# nano_v1_0.net
KiCad netlist of a schematic drawn in EAGLE
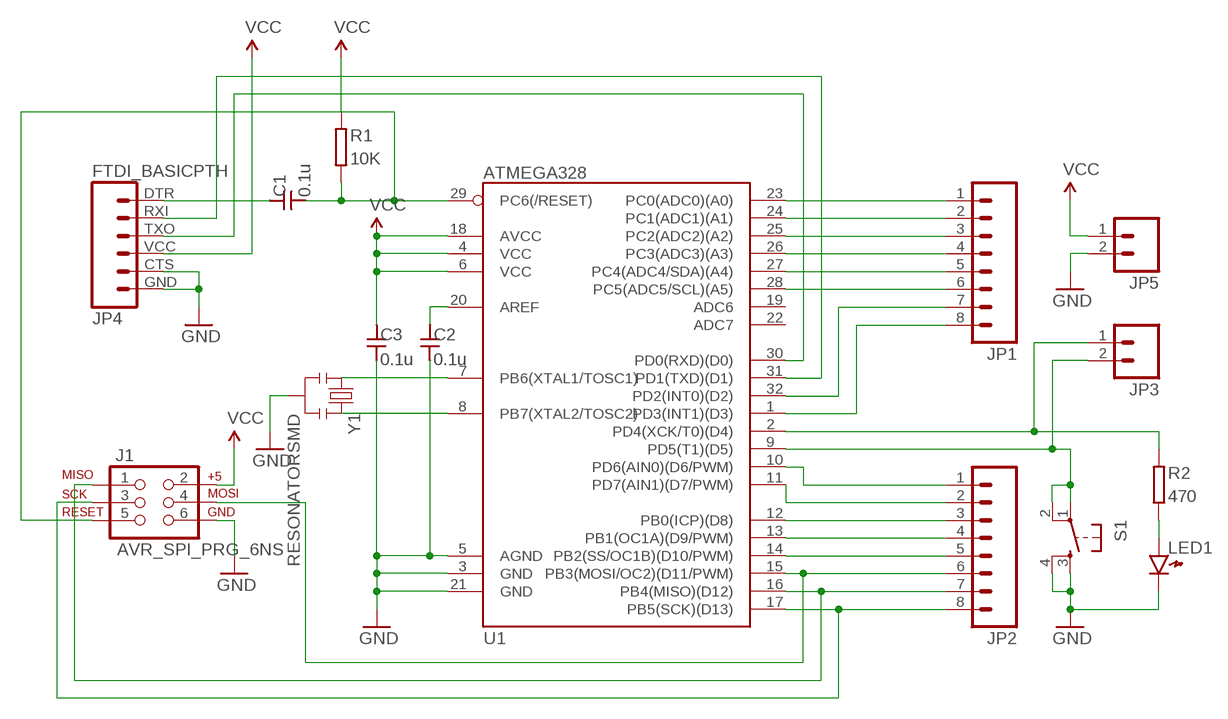
[diagram p0: schematic, sheet 1]

(export (version "E")
  (design (tool "Eeschema 10.0.6"))
  (components
    (comp (ref "C1")
      (value "0.1u")
      (footprint "eagle-import:SMD2012")
      (libsource (lib "eagle-import") (part "CAPACITOR2012"))
    )
    (comp (ref "C2")
      (value "0.1u")
      (footprint "eagle-import:SMD2012")
      (libsource (lib "eagle-import") (part "CAPACITOR2012"))
    )
    (comp (ref "C3")
      (value "0.1u")
      (footprint "eagle-import:SMD2012")
      (libsource (lib "eagle-import") (part "CAPACITOR2012"))
    )
    (comp (ref "J1")
      (value "AVR_SPI_PRG_6NS")
      (footprint "eagle-import:2X3-NS")
      (libsource (lib "eagle-import") (part "AVR_SPI_PRG_6NS"))
    )
    (comp (ref "JP1")
      (value "M081X08")
      (footprint "eagle-import:1X08")
      (libsource (lib "eagle-import") (part "M081X08"))
    )
    (comp (ref "JP2")
      (value "M081X08")
      (footprint "eagle-import:1X08")
      (libsource (lib "eagle-import") (part "M081X08"))
    )
    (comp (ref "JP3")
      (value "M02PTH")
      (footprint "eagle-import:1X02")
      (libsource (lib "eagle-import") (part "M02PTH"))
    )
    (comp (ref "JP4")
      (value "FTDI_BASICPTH")
      (footprint "eagle-import:FTDI_BASIC")
      (libsource (lib "eagle-import") (part "FTDI_BASICPTH"))
    )
    (comp (ref "JP5")
      (value "M021X02_NO_SILK")
      (footprint "eagle-import:1X02_NO_SILK")
      (libsource (lib "eagle-import") (part "M021X02_NO_SILK"))
    )
    (comp (ref "LED1")
      (value "LED2012")
      (footprint "eagle-import:LED2012")
      (libsource (lib "eagle-import") (part "LED2012"))
    )
    (comp (ref "R1")
      (value "10K")
      (footprint "eagle-import:SMD2012")
      (libsource (lib "eagle-import") (part "REGISTOR2012"))
    )
    (comp (ref "R2")
      (value "470")
      (footprint "eagle-import:SMD2012")
      (libsource (lib "eagle-import") (part "REGISTOR2012"))
    )
    (comp (ref "S1")
      (value "TAC_SWITCHSMD")
      (footprint "eagle-import:TACTILE_SWITCH_SMD")
      (libsource (lib "eagle-import") (part "TAC_SWITCHSMD"))
    )
    (comp (ref "U1")
      (value "ATMEGA328")
      (footprint "eagle-import:TQFP32-08")
      (libsource (lib "eagle-import") (part "ATMEGA328"))
    )
    (comp (ref "Y1")
      (value "RESONATORSMD")
      (footprint "eagle-import:RESONATOR-SMD")
      (libsource (lib "eagle-import") (part "RESONATORSMD"))
    )
  )
  (nets
    (net (code "1") (name "GND") (class "Default")
      (node (ref "C2") (pin "2") (pinfunction "2_2") (pintype "passive"))
      (node (ref "C3") (pin "2") (pinfunction "2_2") (pintype "passive"))
      (node (ref "J1") (pin "6") (pinfunction "6_6") (pintype "passive"))
      (node (ref "JP4") (pin "CTS") (pinfunction "5_CTS") (pintype "passive"))
      (node (ref "JP4") (pin "GND") (pinfunction "6_GND") (pintype "passive"))
      (node (ref "JP5") (pin "2") (pinfunction "2_2") (pintype "passive"))
      (node (ref "LED1") (pin "K") (pinfunction "K_K") (pintype "passive"))
      (node (ref "S1") (pin "3") (pinfunction "3_3") (pintype "passive"))
      (node (ref "S1") (pin "4") (pinfunction "4_4") (pintype "passive"))
      (node (ref "U1") (pin "21") (pinfunction "GND_21") (pintype "bidirectional"))
      (node (ref "U1") (pin "3") (pinfunction "GND_3") (pintype "bidirectional"))
      (node (ref "U1") (pin "5") (pinfunction "AGND_5") (pintype "bidirectional"))
      (node (ref "Y1") (pin "2") (pinfunction "2_2") (pintype "passive"))
    )
    (net (code "2") (name "Net-(JP4-1)") (class "Default")
      (node (ref "C1") (pin "1") (pinfunction "1_1") (pintype "passive"))
      (node (ref "JP4") (pin "DTR") (pinfunction "1_DTR") (pintype "passive"))
    )
    (net (code "3") (name "Net-(JP4-2)") (class "Default")
      (node (ref "JP4") (pin "RXI") (pinfunction "2_RXI") (pintype "passive"))
      (node (ref "U1") (pin "31") (pinfunction "PD1(TXD)(D1)_31") (pintype "bidirectional"))
    )
    (net (code "4") (name "Net-(JP4-3)") (class "Default")
      (node (ref "JP4") (pin "TXO") (pinfunction "3_TXO") (pintype "passive"))
      (node (ref "U1") (pin "30") (pinfunction "PD0(RXD)(D0)_30") (pintype "bidirectional"))
    )
    (net (code "5") (name "Net-(LED1-PadA)") (class "Default")
      (node (ref "LED1") (pin "A") (pinfunction "A_A") (pintype "passive"))
      (node (ref "R2") (pin "2") (pinfunction "2_2") (pintype "passive"))
    )
    (net (code "6") (name "Net-(U1-AREF)") (class "Default")
      (node (ref "C2") (pin "1") (pinfunction "1_1") (pintype "passive"))
      (node (ref "U1") (pin "20") (pinfunction "AREF_20") (pintype "bidirectional"))
    )
    (net (code "7") (name "Net-(U1-PB0(ICP)(D8))") (class "Default")
      (node (ref "JP2") (pin "3") (pinfunction "3_3") (pintype "passive"))
      (node (ref "U1") (pin "12") (pinfunction "PB0(ICP)(D8)_12") (pintype "bidirectional"))
    )
    (net (code "8") (name "Net-(U1-PB1(OC1A)(D9{slash}PWM))") (class "Default")
      (node (ref "JP2") (pin "4") (pinfunction "4_4") (pintype "passive"))
      (node (ref "U1") (pin "13") (pinfunction "PB1(OC1A)(D9/PWM)_13") (pintype "bidirectional"))
    )
    (net (code "9") (name "Net-(U1-PB2(SS{slash}OC1B)(D10{slash}PWM))") (class "Default")
      (node (ref "JP2") (pin "5") (pinfunction "5_5") (pintype "passive"))
      (node (ref "U1") (pin "14") (pinfunction "PB2(SS/OC1B)(D10/PWM)_14") (pintype "bidirectional"))
    )
    (net (code "10") (name "Net-(U1-PB3(MOSI{slash}OC2)(D11{slash}PWM))") (class "Default")
      (node (ref "J1") (pin "4") (pinfunction "4_4") (pintype "passive"))
      (node (ref "JP2") (pin "6") (pinfunction "6_6") (pintype "passive"))
      (node (ref "U1") (pin "15") (pinfunction "PB3(MOSI/OC2)(D11/PWM)_15") (pintype "bidirectional"))
    )
    (net (code "11") (name "Net-(U1-PB4(MISO)(D12))") (class "Default")
      (node (ref "J1") (pin "1") (pinfunction "1_1") (pintype "passive"))
      (node (ref "JP2") (pin "7") (pinfunction "7_7") (pintype "passive"))
      (node (ref "U1") (pin "16") (pinfunction "PB4(MISO)(D12)_16") (pintype "bidirectional"))
    )
    (net (code "12") (name "Net-(U1-PB5(SCK)(D13))") (class "Default")
      (node (ref "J1") (pin "3") (pinfunction "3_3") (pintype "passive"))
      (node (ref "JP2") (pin "8") (pinfunction "8_8") (pintype "passive"))
      (node (ref "U1") (pin "17") (pinfunction "PB5(SCK)(D13)_17") (pintype "bidirectional"))
    )
    (net (code "13") (name "Net-(U1-PB6(XTAL1{slash}TOSC1))") (class "Default")
      (node (ref "U1") (pin "7") (pinfunction "PB6(XTAL1/TOSC1)_7") (pintype "bidirectional"))
      (node (ref "Y1") (pin "1") (pinfunction "1_1") (pintype "passive"))
    )
    (net (code "14") (name "Net-(U1-PB7(XTAL2{slash}TOSC2))") (class "Default")
      (node (ref "U1") (pin "8") (pinfunction "PB7(XTAL2/TOSC2)_8") (pintype "bidirectional"))
      (node (ref "Y1") (pin "3") (pinfunction "3_3") (pintype "passive"))
    )
    (net (code "15") (name "Net-(U1-PC0(ADC0)(A0))") (class "Default")
      (node (ref "JP1") (pin "1") (pinfunction "1_1") (pintype "passive"))
      (node (ref "U1") (pin "23") (pinfunction "PC0(ADC0)(A0)_23") (pintype "bidirectional"))
    )
    (net (code "16") (name "Net-(U1-PC1(ADC1)(A1))") (class "Default")
      (node (ref "JP1") (pin "2") (pinfunction "2_2") (pintype "passive"))
      (node (ref "U1") (pin "24") (pinfunction "PC1(ADC1)(A1)_24") (pintype "bidirectional"))
    )
    (net (code "17") (name "Net-(U1-PC2(ADC2)(A2))") (class "Default")
      (node (ref "JP1") (pin "3") (pinfunction "3_3") (pintype "passive"))
      (node (ref "U1") (pin "25") (pinfunction "PC2(ADC2)(A2)_25") (pintype "bidirectional"))
    )
    (net (code "18") (name "Net-(U1-PC3(ADC3)(A3))") (class "Default")
      (node (ref "JP1") (pin "4") (pinfunction "4_4") (pintype "passive"))
      (node (ref "U1") (pin "26") (pinfunction "PC3(ADC3)(A3)_26") (pintype "bidirectional"))
    )
    (net (code "19") (name "Net-(U1-PC4(ADC4{slash}SDA)(A4))") (class "Default")
      (node (ref "JP1") (pin "5") (pinfunction "5_5") (pintype "passive"))
      (node (ref "U1") (pin "27") (pinfunction "PC4(ADC4/SDA)(A4)_27") (pintype "bidirectional"))
    )
    (net (code "20") (name "Net-(U1-PC5(ADC5{slash}SCL)(A5))") (class "Default")
      (node (ref "JP1") (pin "6") (pinfunction "6_6") (pintype "passive"))
      (node (ref "U1") (pin "28") (pinfunction "PC5(ADC5/SCL)(A5)_28") (pintype "bidirectional"))
    )
    (net (code "21") (name "Net-(U1-PC6({slash}RESET))") (class "Default")
      (node (ref "C1") (pin "2") (pinfunction "2_2") (pintype "passive"))
      (node (ref "J1") (pin "5") (pinfunction "5_5") (pintype "passive"))
      (node (ref "R1") (pin "2") (pinfunction "2_2") (pintype "passive"))
      (node (ref "U1") (pin "29") (pinfunction "PC6(/RESET)_29") (pintype "bidirectional"))
    )
    (net (code "22") (name "Net-(U1-PD2(INT0)(D2))") (class "Default")
      (node (ref "JP1") (pin "7") (pinfunction "7_7") (pintype "passive"))
      (node (ref "U1") (pin "32") (pinfunction "PD2(INT0)(D2)_32") (pintype "bidirectional"))
    )
    (net (code "23") (name "Net-(U1-PD3(INT1)(D3))") (class "Default")
      (node (ref "JP1") (pin "8") (pinfunction "8_8") (pintype "passive"))
      (node (ref "U1") (pin "1") (pinfunction "PD3(INT1)(D3)_1") (pintype "bidirectional"))
    )
    (net (code "24") (name "Net-(U1-PD4(XCK{slash}T0)(D4))") (class "Default")
      (node (ref "JP3") (pin "1") (pinfunction "1_1") (pintype "passive"))
      (node (ref "R2") (pin "1") (pinfunction "1_1") (pintype "passive"))
      (node (ref "U1") (pin "2") (pinfunction "PD4(XCK/T0)(D4)_2") (pintype "bidirectional"))
    )
    (net (code "25") (name "Net-(U1-PD5(T1)(D5))") (class "Default")
      (node (ref "JP3") (pin "2") (pinfunction "2_2") (pintype "passive"))
      (node (ref "S1") (pin "1") (pinfunction "1_1") (pintype "passive"))
      (node (ref "S1") (pin "2") (pinfunction "2_2") (pintype "passive"))
      (node (ref "U1") (pin "9") (pinfunction "PD5(T1)(D5)_9") (pintype "bidirectional"))
    )
    (net (code "26") (name "Net-(U1-PD6(AIN0)(D6{slash}PWM))") (class "Default")
      (node (ref "JP2") (pin "1") (pinfunction "1_1") (pintype "passive"))
      (node (ref "U1") (pin "10") (pinfunction "PD6(AIN0)(D6/PWM)_10") (pintype "bidirectional"))
    )
    (net (code "27") (name "Net-(U1-PD7(AIN1)(D7{slash}PWM))") (class "Default")
      (node (ref "JP2") (pin "2") (pinfunction "2_2") (pintype "passive"))
      (node (ref "U1") (pin "11") (pinfunction "PD7(AIN1)(D7/PWM)_11") (pintype "bidirectional"))
    )
    (net (code "28") (name "VCC") (class "Default")
      (node (ref "C3") (pin "1") (pinfunction "1_1") (pintype "passive"))
      (node (ref "J1") (pin "2") (pinfunction "2_2") (pintype "passive"))
      (node (ref "JP4") (pin "VCC") (pinfunction "4_VCC") (pintype "passive"))
      (node (ref "JP5") (pin "1") (pinfunction "1_1") (pintype "passive"))
      (node (ref "R1") (pin "1") (pinfunction "1_1") (pintype "passive"))
      (node (ref "U1") (pin "18") (pinfunction "AVCC_18") (pintype "bidirectional"))
      (node (ref "U1") (pin "4") (pinfunction "VCC_4") (pintype "bidirectional"))
      (node (ref "U1") (pin "6") (pinfunction "VCC_6") (pintype "bidirectional"))
    )
    (net (code "29") (name "unconnected-(U1-ADC6-Pad19)") (class "Default")
      (node (ref "U1") (pin "19") (pinfunction "ADC6_19") (pintype "bidirectional"))
    )
    (net (code "30") (name "unconnected-(U1-ADC7-Pad22)") (class "Default")
      (node (ref "U1") (pin "22") (pinfunction "ADC7_22") (pintype "bidirectional"))
    )
  )
)
